# MiniARMBoard.net
KiCad netlist of a schematic drawn in EAGLE
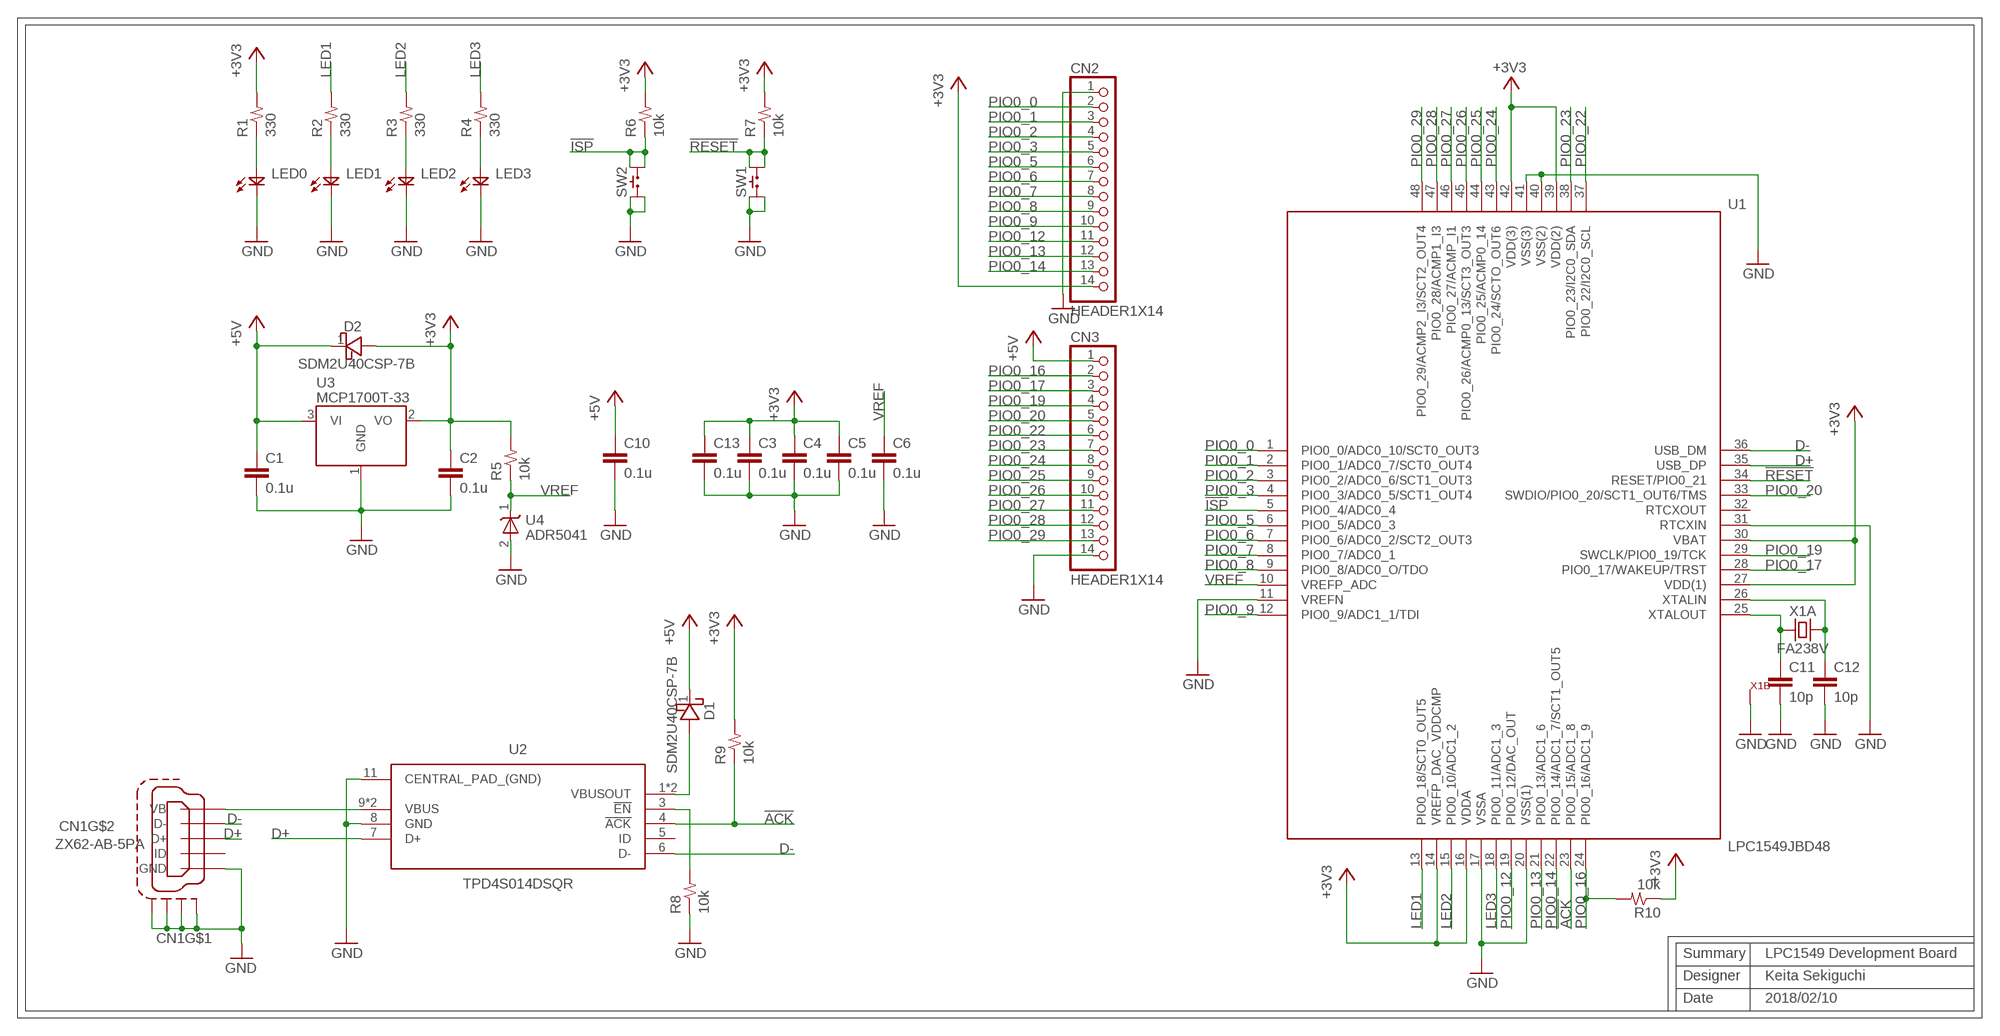
[diagram p0: schematic, sheet 1]

(export (version "E")
  (design (tool "Eeschema 10.0.6"))
  (components
    (comp (ref "C1")
      (value "0.1u")
      (footprint "eagle-import:C1005")
      (libsource (lib "eagle-import") (part "C1005"))
    )
    (comp (ref "C2")
      (value "0.1u")
      (footprint "eagle-import:C1005")
      (libsource (lib "eagle-import") (part "C1005"))
    )
    (comp (ref "C3")
      (value "0.1u")
      (footprint "eagle-import:C1005")
      (libsource (lib "eagle-import") (part "C1005"))
    )
    (comp (ref "C4")
      (value "0.1u")
      (footprint "eagle-import:C1005")
      (libsource (lib "eagle-import") (part "C1005"))
    )
    (comp (ref "C5")
      (value "0.1u")
      (footprint "eagle-import:C1005")
      (libsource (lib "eagle-import") (part "C1005"))
    )
    (comp (ref "C6")
      (value "0.1u")
      (footprint "eagle-import:C1005")
      (libsource (lib "eagle-import") (part "C1005"))
    )
    (comp (ref "C10")
      (value "0.1u")
      (footprint "eagle-import:C1005")
      (libsource (lib "eagle-import") (part "C1005"))
    )
    (comp (ref "C11")
      (value "10p")
      (footprint "eagle-import:C1005")
      (libsource (lib "eagle-import") (part "C1005"))
    )
    (comp (ref "C12")
      (value "10p")
      (footprint "eagle-import:C1005")
      (libsource (lib "eagle-import") (part "C1005"))
    )
    (comp (ref "C13")
      (value "0.1u")
      (footprint "eagle-import:C1005")
      (libsource (lib "eagle-import") (part "C1005"))
    )
    (comp (ref "CN1")
      (value "ZX62-AB-5PA")
      (footprint "eagle-import:J_USB_MICROAB_HIROSE_ZX62-AB-5PA")
      (libsource (lib "eagle-import") (part "J_USB_MICROAB_HIROSE_ZX62-AB-5PA"))
    )
    (comp (ref "CN2")
      (value "HEADER1X14")
      (footprint "eagle-import:1X14_ROUND")
      (libsource (lib "eagle-import") (part "HEADER1X14"))
    )
    (comp (ref "CN3")
      (value "HEADER1X14")
      (footprint "eagle-import:1X14_ROUND")
      (libsource (lib "eagle-import") (part "HEADER1X14"))
    )
    (comp (ref "D1")
      (value "SDM2U40CSP-7B")
      (footprint "eagle-import:X3-WLB1608-2")
      (libsource (lib "eagle-import") (part "SDM2U40CSP-7B"))
    )
    (comp (ref "D2")
      (value "SDM2U40CSP-7B")
      (footprint "eagle-import:X3-WLB1608-2")
      (libsource (lib "eagle-import") (part "SDM2U40CSP-7B"))
    )
    (comp (ref "LED0")
      (value "LED1608")
      (footprint "eagle-import:LED1608")
      (libsource (lib "eagle-import") (part "LED1608"))
    )
    (comp (ref "LED1")
      (value "LED1608")
      (footprint "eagle-import:LED1608")
      (libsource (lib "eagle-import") (part "LED1608"))
    )
    (comp (ref "LED2")
      (value "LED1608")
      (footprint "eagle-import:LED1608")
      (libsource (lib "eagle-import") (part "LED1608"))
    )
    (comp (ref "LED3")
      (value "LED1608")
      (footprint "eagle-import:LED1608")
      (libsource (lib "eagle-import") (part "LED1608"))
    )
    (comp (ref "R1")
      (value "330")
      (footprint "eagle-import:R1005")
      (libsource (lib "eagle-import") (part "R1005"))
    )
    (comp (ref "R2")
      (value "330")
      (footprint "eagle-import:R1005")
      (libsource (lib "eagle-import") (part "R1005"))
    )
    (comp (ref "R3")
      (value "330")
      (footprint "eagle-import:R1005")
      (libsource (lib "eagle-import") (part "R1005"))
    )
    (comp (ref "R4")
      (value "330")
      (footprint "eagle-import:R1005")
      (libsource (lib "eagle-import") (part "R1005"))
    )
    (comp (ref "R5")
      (value "10k")
      (footprint "eagle-import:R1005")
      (libsource (lib "eagle-import") (part "R1005"))
    )
    (comp (ref "R6")
      (value "10k")
      (footprint "eagle-import:R1005")
      (libsource (lib "eagle-import") (part "R1005"))
    )
    (comp (ref "R7")
      (value "10k")
      (footprint "eagle-import:R1005")
      (libsource (lib "eagle-import") (part "R1005"))
    )
    (comp (ref "R8")
      (value "10k")
      (footprint "eagle-import:R1005")
      (libsource (lib "eagle-import") (part "R1005"))
    )
    (comp (ref "R9")
      (value "10k")
      (footprint "eagle-import:R1005")
      (libsource (lib "eagle-import") (part "R1005"))
    )
    (comp (ref "R10")
      (value "10k")
      (footprint "eagle-import:R1005")
      (libsource (lib "eagle-import") (part "R1005"))
    )
    (comp (ref "SW1")
      (value "SKRP")
      (footprint "eagle-import:SKRP")
      (libsource (lib "eagle-import") (part "SKRP"))
    )
    (comp (ref "SW2")
      (value "SKRP")
      (footprint "eagle-import:SKRP")
      (libsource (lib "eagle-import") (part "SKRP"))
    )
    (comp (ref "U1")
      (value "LPC1549JBD48")
      (footprint "eagle-import:QFP48")
      (libsource (lib "eagle-import") (part "LPC1549JBD48"))
    )
    (comp (ref "U2")
      (value "TPD4S014DSQR")
      (footprint "eagle-import:SON40P200X200X80-11N")
      (fields (field (name "RS_PART_NUMBER") "7422968"))
      (libsource (lib "eagle-import") (part "TPD4S014DSQR"))
    )
    (comp (ref "U3")
      (value "MCP1700T-33")
      (footprint "eagle-import:SOT23-3")
      (libsource (lib "eagle-import") (part "MCP1700T-33"))
    )
    (comp (ref "U4")
      (value "ADR5041")
      (footprint "eagle-import:SC70-3")
      (libsource (lib "eagle-import") (part "ADR5041"))
    )
    (comp (ref "X1")
      (value "FA238V")
      (footprint "eagle-import:EPSON_FA238V")
      (libsource (lib "eagle-import") (part "FA238V"))
    )
  )
  (nets
    (net (code "1") (name "+3V3") (class "Default")
      (node (ref "C13") (pin "1") (pinfunction "1_1") (pintype "passive"))
      (node (ref "C2") (pin "1") (pinfunction "1_1") (pintype "passive"))
      (node (ref "C3") (pin "1") (pinfunction "1_1") (pintype "passive"))
      (node (ref "C4") (pin "1") (pinfunction "1_1") (pintype "passive"))
      (node (ref "C5") (pin "1") (pinfunction "1_1") (pintype "passive"))
      (node (ref "CN2") (pin "14") (pinfunction "14_14") (pintype "passive"))
      (node (ref "D2") (pin "2") (pinfunction "A_2") (pintype "passive"))
      (node (ref "R1") (pin "2") (pinfunction "2_2") (pintype "passive"))
      (node (ref "R10") (pin "1") (pinfunction "1_1") (pintype "passive"))
      (node (ref "R5") (pin "2") (pinfunction "2_2") (pintype "passive"))
      (node (ref "R6") (pin "2") (pinfunction "2_2") (pintype "passive"))
      (node (ref "R7") (pin "2") (pinfunction "2_2") (pintype "passive"))
      (node (ref "R9") (pin "2") (pinfunction "2_2") (pintype "passive"))
      (node (ref "U1") (pin "14") (pinfunction "VREFP_DAC_VDDCMP_14") (pintype "passive"))
      (node (ref "U1") (pin "16") (pinfunction "VDDA_16") (pintype "passive"))
      (node (ref "U1") (pin "27") (pinfunction "VDD(1)_27") (pintype "passive"))
      (node (ref "U1") (pin "30") (pinfunction "VBAT_30") (pintype "passive"))
      (node (ref "U1") (pin "39") (pinfunction "VDD(2)_39") (pintype "passive"))
      (node (ref "U1") (pin "42") (pinfunction "VDD(3)_42") (pintype "passive"))
      (node (ref "U3") (pin "2") (pinfunction "VO_2") (pintype "bidirectional"))
    )
    (net (code "2") (name "+5V") (class "Default")
      (node (ref "C1") (pin "1") (pinfunction "1_1") (pintype "passive"))
      (node (ref "C10") (pin "1") (pinfunction "1_1") (pintype "passive"))
      (node (ref "CN3") (pin "1") (pinfunction "1_1") (pintype "passive"))
      (node (ref "D1") (pin "1") (pinfunction "K_1") (pintype "passive"))
      (node (ref "D2") (pin "1") (pinfunction "K_1") (pintype "passive"))
      (node (ref "U3") (pin "3") (pinfunction "VI_3") (pintype "bidirectional"))
    )
    (net (code "3") (name "/D+") (class "Default")
      (node (ref "CN1") (pin "P$3") (pinfunction "D+_P$3") (pintype "passive"))
      (node (ref "U1") (pin "35") (pinfunction "USB_DP_35") (pintype "passive"))
      (node (ref "U2") (pin "7") (pinfunction "D+_7") (pintype "passive"))
    )
    (net (code "4") (name "/D-") (class "Default")
      (node (ref "CN1") (pin "P$2") (pinfunction "D-_P$2") (pintype "passive"))
      (node (ref "U1") (pin "36") (pinfunction "USB_DM_36") (pintype "passive"))
      (node (ref "U2") (pin "6") (pinfunction "D-_6") (pintype "passive"))
    )
    (net (code "5") (name "/LED1") (class "Default")
      (node (ref "R2") (pin "2") (pinfunction "2_2") (pintype "passive"))
      (node (ref "U1") (pin "13") (pinfunction "PIO0_18/SCT0_OUT5_13") (pintype "passive"))
    )
    (net (code "6") (name "/LED2") (class "Default")
      (node (ref "R3") (pin "2") (pinfunction "2_2") (pintype "passive"))
      (node (ref "U1") (pin "15") (pinfunction "PIO0_10/ADC1_2_15") (pintype "passive"))
    )
    (net (code "7") (name "/LED3") (class "Default")
      (node (ref "R4") (pin "2") (pinfunction "2_2") (pintype "passive"))
      (node (ref "U1") (pin "18") (pinfunction "PIO0_11/ADC1_3_18") (pintype "passive"))
    )
    (net (code "8") (name "/PIO0_0") (class "Default")
      (node (ref "CN2") (pin "2") (pinfunction "2_2") (pintype "passive"))
      (node (ref "U1") (pin "1") (pinfunction "PIO0_0/ADC0_10/SCT0_OUT3_1") (pintype "passive"))
    )
    (net (code "9") (name "/PIO0_1") (class "Default")
      (node (ref "CN2") (pin "3") (pinfunction "3_3") (pintype "passive"))
      (node (ref "U1") (pin "2") (pinfunction "PIO0_1/ADC0_7/SCT0_OUT4_2") (pintype "passive"))
    )
    (net (code "10") (name "/PIO0_2") (class "Default")
      (node (ref "CN2") (pin "4") (pinfunction "4_4") (pintype "passive"))
      (node (ref "U1") (pin "3") (pinfunction "PIO0_2/ADC0_6/SCT1_OUT3_3") (pintype "passive"))
    )
    (net (code "11") (name "/PIO0_3") (class "Default")
      (node (ref "CN2") (pin "5") (pinfunction "5_5") (pintype "passive"))
      (node (ref "U1") (pin "4") (pinfunction "PIO0_3/ADC0_5/SCT1_OUT4_4") (pintype "passive"))
    )
    (net (code "12") (name "/PIO0_5") (class "Default")
      (node (ref "CN2") (pin "6") (pinfunction "6_6") (pintype "passive"))
      (node (ref "U1") (pin "6") (pinfunction "PIO0_5/ADC0_3_6") (pintype "passive"))
    )
    (net (code "13") (name "/PIO0_6") (class "Default")
      (node (ref "CN2") (pin "7") (pinfunction "7_7") (pintype "passive"))
      (node (ref "U1") (pin "7") (pinfunction "PIO0_6/ADC0_2/SCT2_OUT3_7") (pintype "passive"))
    )
    (net (code "14") (name "/PIO0_7") (class "Default")
      (node (ref "CN2") (pin "8") (pinfunction "8_8") (pintype "passive"))
      (node (ref "U1") (pin "8") (pinfunction "PIO0_7/ADC0_1_8") (pintype "passive"))
    )
    (net (code "15") (name "/PIO0_8") (class "Default")
      (node (ref "CN2") (pin "9") (pinfunction "9_9") (pintype "passive"))
      (node (ref "U1") (pin "9") (pinfunction "PIO0_8/ADC0_O/TDO_9") (pintype "passive"))
    )
    (net (code "16") (name "/PIO0_9") (class "Default")
      (node (ref "CN2") (pin "10") (pinfunction "10_10") (pintype "passive"))
      (node (ref "U1") (pin "12") (pinfunction "PIO0_9/ADC1_1/TDI_12") (pintype "passive"))
    )
    (net (code "17") (name "/PIO0_12") (class "Default")
      (node (ref "CN2") (pin "11") (pinfunction "11_11") (pintype "passive"))
      (node (ref "U1") (pin "19") (pinfunction "PIO0_12/DAC_OUT_19") (pintype "passive"))
    )
    (net (code "18") (name "/PIO0_13") (class "Default")
      (node (ref "CN2") (pin "12") (pinfunction "12_12") (pintype "passive"))
      (node (ref "U1") (pin "21") (pinfunction "PIO0_13/ADC1_6_21") (pintype "passive"))
    )
    (net (code "19") (name "/PIO0_14") (class "Default")
      (node (ref "CN2") (pin "13") (pinfunction "13_13") (pintype "passive"))
      (node (ref "U1") (pin "22") (pinfunction "PIO0_14/ADC1_7/SCT1_OUT5_22") (pintype "passive"))
    )
    (net (code "20") (name "/PIO0_16") (class "Default")
      (node (ref "CN3") (pin "2") (pinfunction "2_2") (pintype "passive"))
      (node (ref "R10") (pin "2") (pinfunction "2_2") (pintype "passive"))
      (node (ref "U1") (pin "24") (pinfunction "PIO0_16/ADC1_9_24") (pintype "passive"))
    )
    (net (code "21") (name "/PIO0_17") (class "Default")
      (node (ref "CN3") (pin "3") (pinfunction "3_3") (pintype "passive"))
      (node (ref "U1") (pin "28") (pinfunction "PIO0_17/WAKEUP/TRST_28") (pintype "passive"))
    )
    (net (code "22") (name "/PIO0_19") (class "Default")
      (node (ref "CN3") (pin "4") (pinfunction "4_4") (pintype "passive"))
      (node (ref "U1") (pin "29") (pinfunction "SWCLK/PIO0_19/TCK_29") (pintype "passive"))
    )
    (net (code "23") (name "/PIO0_20") (class "Default")
      (node (ref "CN3") (pin "5") (pinfunction "5_5") (pintype "passive"))
      (node (ref "U1") (pin "33") (pinfunction "SWDIO/PIO0_20/SCT1_OUT6/TMS_33") (pintype "passive"))
    )
    (net (code "24") (name "/PIO0_22") (class "Default")
      (node (ref "CN3") (pin "6") (pinfunction "6_6") (pintype "passive"))
      (node (ref "U1") (pin "37") (pinfunction "PIO0_22/I2C0_SCL_37") (pintype "passive"))
    )
    (net (code "25") (name "/PIO0_23") (class "Default")
      (node (ref "CN3") (pin "7") (pinfunction "7_7") (pintype "passive"))
      (node (ref "U1") (pin "38") (pinfunction "PIO0_23/I2C0_SDA_38") (pintype "passive"))
    )
    (net (code "26") (name "/PIO0_24") (class "Default")
      (node (ref "CN3") (pin "8") (pinfunction "8_8") (pintype "passive"))
      (node (ref "U1") (pin "43") (pinfunction "PIO0_24/SCTO_OUT6_43") (pintype "passive"))
    )
    (net (code "27") (name "/PIO0_25") (class "Default")
      (node (ref "CN3") (pin "9") (pinfunction "9_9") (pintype "passive"))
      (node (ref "U1") (pin "44") (pinfunction "PIO0_25/ACMP0_14_44") (pintype "passive"))
    )
    (net (code "28") (name "/PIO0_26") (class "Default")
      (node (ref "CN3") (pin "10") (pinfunction "10_10") (pintype "passive"))
      (node (ref "U1") (pin "45") (pinfunction "PIO0_26/ACMP0_13/SCT3_OUT3_45") (pintype "passive"))
    )
    (net (code "29") (name "/PIO0_27") (class "Default")
      (node (ref "CN3") (pin "11") (pinfunction "11_11") (pintype "passive"))
      (node (ref "U1") (pin "46") (pinfunction "PIO0_27/ACMP_I1_46") (pintype "passive"))
    )
    (net (code "30") (name "/PIO0_28") (class "Default")
      (node (ref "CN3") (pin "12") (pinfunction "12_12") (pintype "passive"))
      (node (ref "U1") (pin "47") (pinfunction "PIO0_28/ACMP1_I3_47") (pintype "passive"))
    )
    (net (code "31") (name "/PIO0_29") (class "Default")
      (node (ref "CN3") (pin "13") (pinfunction "13_13") (pintype "passive"))
      (node (ref "U1") (pin "48") (pinfunction "PIO0_29/ACMP2_I3/SCT2_OUT4_48") (pintype "passive"))
    )
    (net (code "32") (name "/VREF") (class "Default")
      (node (ref "C6") (pin "1") (pinfunction "1_1") (pintype "passive"))
      (node (ref "R5") (pin "1") (pinfunction "1_1") (pintype "passive"))
      (node (ref "U1") (pin "10") (pinfunction "VREFP_ADC_10") (pintype "passive"))
      (node (ref "U4") (pin "1") (pinfunction "K_1") (pintype "passive"))
    )
    (net (code "33") (name "/~{ACK}") (class "Default")
      (node (ref "R9") (pin "1") (pinfunction "1_1") (pintype "passive"))
      (node (ref "U1") (pin "23") (pinfunction "PIO0_15/ADC1_8_23") (pintype "passive"))
      (node (ref "U2") (pin "4") (pinfunction "~{ACK}_4") (pintype "passive"))
    )
    (net (code "34") (name "/~{ISP}") (class "Default")
      (node (ref "R6") (pin "1") (pinfunction "1_1") (pintype "passive"))
      (node (ref "SW2") (pin "B1") (pinfunction "B1_B1") (pintype "passive"))
      (node (ref "SW2") (pin "B2") (pinfunction "B2_B2") (pintype "passive"))
      (node (ref "U1") (pin "5") (pinfunction "PIO0_4/ADC0_4_5") (pintype "passive"))
    )
    (net (code "35") (name "/~{RESET}") (class "Default")
      (node (ref "R7") (pin "1") (pinfunction "1_1") (pintype "passive"))
      (node (ref "SW1") (pin "B1") (pinfunction "B1_B1") (pintype "passive"))
      (node (ref "SW1") (pin "B2") (pinfunction "B2_B2") (pintype "passive"))
      (node (ref "U1") (pin "34") (pinfunction "RESET/PIO0_21_34") (pintype "passive"))
    )
    (net (code "36") (name "GND") (class "Default")
      (node (ref "C1") (pin "2") (pinfunction "2_2") (pintype "passive"))
      (node (ref "C10") (pin "2") (pinfunction "2_2") (pintype "passive"))
      (node (ref "C11") (pin "2") (pinfunction "2_2") (pintype "passive"))
      (node (ref "C12") (pin "2") (pinfunction "2_2") (pintype "passive"))
      (node (ref "C13") (pin "2") (pinfunction "2_2") (pintype "passive"))
      (node (ref "C2") (pin "2") (pinfunction "2_2") (pintype "passive"))
      (node (ref "C3") (pin "2") (pinfunction "2_2") (pintype "passive"))
      (node (ref "C4") (pin "2") (pinfunction "2_2") (pintype "passive"))
      (node (ref "C5") (pin "2") (pinfunction "2_2") (pintype "passive"))
      (node (ref "C6") (pin "2") (pinfunction "2_2") (pintype "passive"))
      (node (ref "CN1") (pin "P$5") (pinfunction "GND_P$5") (pintype "passive"))
      (node (ref "CN1") (pin "SHIELD1") (pinfunction "S1_SHIELD1") (pintype "passive"))
      (node (ref "CN1") (pin "SHIELD2") (pinfunction "S2_SHIELD2") (pintype "passive"))
      (node (ref "CN1") (pin "SHIELD3") (pinfunction "S3_SHIELD3") (pintype "passive"))
      (node (ref "CN1") (pin "SHIELD4") (pinfunction "S4_SHIELD4") (pintype "passive"))
      (node (ref "CN2") (pin "1") (pinfunction "1_1") (pintype "passive"))
      (node (ref "CN3") (pin "14") (pinfunction "14_14") (pintype "passive"))
      (node (ref "LED0") (pin "K") (pinfunction "K_K") (pintype "passive"))
      (node (ref "LED1") (pin "K") (pinfunction "K_K") (pintype "passive"))
      (node (ref "LED2") (pin "K") (pinfunction "K_K") (pintype "passive"))
      (node (ref "LED3") (pin "K") (pinfunction "K_K") (pintype "passive"))
      (node (ref "R8") (pin "1") (pinfunction "1_1") (pintype "passive"))
      (node (ref "SW1") (pin "A1") (pinfunction "A1_A1") (pintype "passive"))
      (node (ref "SW1") (pin "A2") (pinfunction "A2_A2") (pintype "passive"))
      (node (ref "SW2") (pin "A1") (pinfunction "A1_A1") (pintype "passive"))
      (node (ref "SW2") (pin "A2") (pinfunction "A2_A2") (pintype "passive"))
      (node (ref "U1") (pin "11") (pinfunction "VREFN_11") (pintype "passive"))
      (node (ref "U1") (pin "17") (pinfunction "VSSA_17") (pintype "passive"))
      (node (ref "U1") (pin "20") (pinfunction "VSS(1)_20") (pintype "passive"))
      (node (ref "U1") (pin "31") (pinfunction "RTCXIN_31") (pintype "passive"))
      (node (ref "U1") (pin "40") (pinfunction "VSS(2)_40") (pintype "passive"))
      (node (ref "U1") (pin "41") (pinfunction "VSS(3)_41") (pintype "passive"))
      (node (ref "U2") (pin "11") (pinfunction "CENTRAL_PAD_(GND)_11") (pintype "passive"))
      (node (ref "U2") (pin "8") (pinfunction "GND_8") (pintype "passive"))
      (node (ref "U3") (pin "1") (pinfunction "GND_1") (pintype "bidirectional"))
      (node (ref "U4") (pin "2") (pinfunction "A_2") (pintype "passive"))
      (node (ref "X1") (pin "2") (pinfunction "1_2") (pintype "bidirectional"))
      (node (ref "X1") (pin "4") (pinfunction "1_4") (pintype "bidirectional"))
    )
    (net (code "37") (name "Net-(CN1B-VB)") (class "Default")
      (node (ref "CN1") (pin "P$1") (pinfunction "VB_P$1") (pintype "passive"))
      (node (ref "U2") (pin "10") (pinfunction "VBUS_10") (pintype "passive"))
      (node (ref "U2") (pin "9") (pinfunction "VBUS_9") (pintype "passive"))
    )
    (net (code "38") (name "Net-(D1-A)") (class "Default")
      (node (ref "D1") (pin "2") (pinfunction "A_2") (pintype "passive"))
      (node (ref "U2") (pin "1") (pinfunction "VBUSOUT_1") (pintype "passive"))
      (node (ref "U2") (pin "2") (pinfunction "VBUSOUT_2") (pintype "passive"))
    )
    (net (code "39") (name "Net-(LED0-PadA)") (class "Default")
      (node (ref "LED0") (pin "A") (pinfunction "A_A") (pintype "passive"))
      (node (ref "R1") (pin "1") (pinfunction "1_1") (pintype "passive"))
    )
    (net (code "40") (name "Net-(LED1-PadA)") (class "Default")
      (node (ref "LED1") (pin "A") (pinfunction "A_A") (pintype "passive"))
      (node (ref "R2") (pin "1") (pinfunction "1_1") (pintype "passive"))
    )
    (net (code "41") (name "Net-(LED2-PadA)") (class "Default")
      (node (ref "LED2") (pin "A") (pinfunction "A_A") (pintype "passive"))
      (node (ref "R3") (pin "1") (pinfunction "1_1") (pintype "passive"))
    )
    (net (code "42") (name "Net-(LED3-PadA)") (class "Default")
      (node (ref "LED3") (pin "A") (pinfunction "A_A") (pintype "passive"))
      (node (ref "R4") (pin "1") (pinfunction "1_1") (pintype "passive"))
    )
    (net (code "43") (name "Net-(U1-XTALIN)") (class "Default")
      (node (ref "C12") (pin "1") (pinfunction "1_1") (pintype "passive"))
      (node (ref "U1") (pin "26") (pinfunction "XTALIN_26") (pintype "passive"))
      (node (ref "X1") (pin "3") (pinfunction "3_3") (pintype "passive"))
    )
    (net (code "44") (name "Net-(U1-XTALOUT)") (class "Default")
      (node (ref "C11") (pin "1") (pinfunction "1_1") (pintype "passive"))
      (node (ref "U1") (pin "25") (pinfunction "XTALOUT_25") (pintype "passive"))
      (node (ref "X1") (pin "1") (pinfunction "1_1") (pintype "passive"))
    )
    (net (code "45") (name "Net-(U2-~{EN})") (class "Default")
      (node (ref "R8") (pin "2") (pinfunction "2_2") (pintype "passive"))
      (node (ref "U2") (pin "3") (pinfunction "~{EN}_3") (pintype "passive"))
    )
    (net (code "46") (name "unconnected-(CN1B-ID-PadP$4)") (class "Default")
      (node (ref "CN1") (pin "P$4") (pinfunction "ID_P$4") (pintype "passive"))
    )
    (net (code "47") (name "unconnected-(U1-RTCXOUT-Pad32)") (class "Default")
      (node (ref "U1") (pin "32") (pinfunction "RTCXOUT_32") (pintype "passive"))
    )
    (net (code "48") (name "unconnected-(U2-ID-Pad5)") (class "Default")
      (node (ref "U2") (pin "5") (pinfunction "ID_5") (pintype "passive"))
    )
  )
)
